# kiosk_buttons_revA.net
KiCad netlist of a schematic drawn in EAGLE
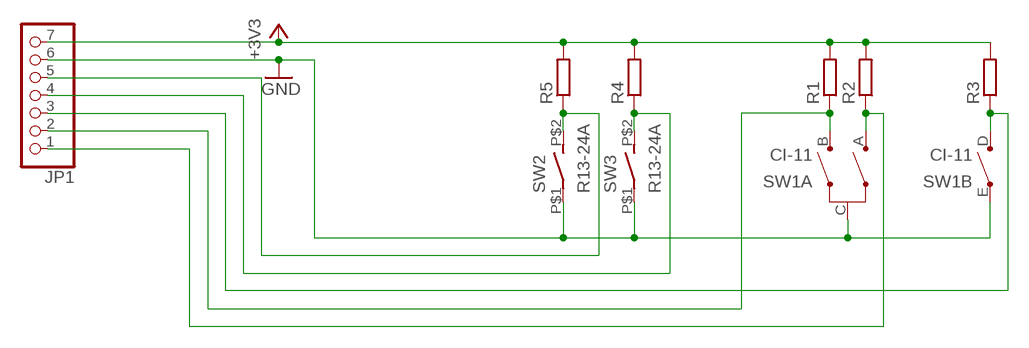
[diagram p0: schematic, sheet 1]

(export (version "E")
  (design (tool "Eeschema 10.0.6"))
  (components
    (comp (ref "JP1")
      (value "PINHD-1X7")
      (footprint "eagle-import:1X07")
      (libsource (lib "eagle-import") (part "PINHD-1X7"))
    )
    (comp (ref "R1")
      (value "R-EU_0204/2V")
      (footprint "eagle-import:0204V")
      (libsource (lib "eagle-import") (part "R-EU_0204/2V"))
    )
    (comp (ref "R2")
      (value "R-EU_0204/2V")
      (footprint "eagle-import:0204V")
      (libsource (lib "eagle-import") (part "R-EU_0204/2V"))
    )
    (comp (ref "R3")
      (value "R-EU_0204/2V")
      (footprint "eagle-import:0204V")
      (libsource (lib "eagle-import") (part "R-EU_0204/2V"))
    )
    (comp (ref "R4")
      (value "R-EU_0204/2V")
      (footprint "eagle-import:0204V")
      (libsource (lib "eagle-import") (part "R-EU_0204/2V"))
    )
    (comp (ref "R5")
      (value "R-EU_0204/2V")
      (footprint "eagle-import:0204V")
      (libsource (lib "eagle-import") (part "R-EU_0204/2V"))
    )
    (comp (ref "SW1")
      (value "CI-11")
      (footprint "eagle-import:CI-11")
      (libsource (lib "eagle-import") (part "CI-11"))
    )
    (comp (ref "SW2")
      (value "R13-24A")
      (footprint "eagle-import:R13-24")
      (fields (field (name "MF") "SCI"))
      (libsource (lib "eagle-import") (part "R13-24A"))
    )
    (comp (ref "SW3")
      (value "R13-24A")
      (footprint "eagle-import:R13-24")
      (fields (field (name "MF") "SCI"))
      (libsource (lib "eagle-import") (part "R13-24A"))
    )
  )
  (nets
    (net (code "1") (name "+3V3") (class "Default")
      (node (ref "JP1") (pin "7") (pinfunction "7_7") (pintype "passive"))
      (node (ref "R1") (pin "2") (pinfunction "2_2") (pintype "passive"))
      (node (ref "R2") (pin "2") (pinfunction "2_2") (pintype "passive"))
      (node (ref "R3") (pin "2") (pinfunction "2_2") (pintype "passive"))
      (node (ref "R4") (pin "2") (pinfunction "2_2") (pintype "passive"))
      (node (ref "R5") (pin "2") (pinfunction "2_2") (pintype "passive"))
    )
    (net (code "2") (name "GND") (class "Default")
      (node (ref "JP1") (pin "6") (pinfunction "6_6") (pintype "passive"))
      (node (ref "SW1") (pin "C") (pinfunction "C_C") (pintype "passive"))
      (node (ref "SW1") (pin "E") (pinfunction "E_E") (pintype "passive"))
      (node (ref "SW2") (pin "P$1") (pinfunction "P_P$1") (pintype "passive"))
      (node (ref "SW3") (pin "P$1") (pinfunction "P_P$1") (pintype "passive"))
    )
    (net (code "3") (name "Net-(JP1-Pad1)") (class "Default")
      (node (ref "JP1") (pin "1") (pinfunction "1_1") (pintype "passive"))
      (node (ref "R2") (pin "1") (pinfunction "1_1") (pintype "passive"))
      (node (ref "SW1") (pin "A") (pinfunction "A_A") (pintype "passive"))
    )
    (net (code "4") (name "Net-(JP1-Pad2)") (class "Default")
      (node (ref "JP1") (pin "2") (pinfunction "2_2") (pintype "passive"))
      (node (ref "R1") (pin "1") (pinfunction "1_1") (pintype "passive"))
      (node (ref "SW1") (pin "B") (pinfunction "B_B") (pintype "passive"))
    )
    (net (code "5") (name "Net-(JP1-Pad3)") (class "Default")
      (node (ref "JP1") (pin "3") (pinfunction "3_3") (pintype "passive"))
      (node (ref "R3") (pin "1") (pinfunction "1_1") (pintype "passive"))
      (node (ref "SW1") (pin "D") (pinfunction "D_D") (pintype "passive"))
    )
    (net (code "6") (name "Net-(SW2-S)") (class "Default")
      (node (ref "JP1") (pin "5") (pinfunction "5_5") (pintype "passive"))
      (node (ref "R5") (pin "1") (pinfunction "1_1") (pintype "passive"))
      (node (ref "SW2") (pin "P$2") (pinfunction "S_P$2") (pintype "passive"))
    )
    (net (code "7") (name "Net-(SW3-S)") (class "Default")
      (node (ref "JP1") (pin "4") (pinfunction "4_4") (pintype "passive"))
      (node (ref "R4") (pin "1") (pinfunction "1_1") (pintype "passive"))
      (node (ref "SW3") (pin "P$2") (pinfunction "S_P$2") (pintype "passive"))
    )
  )
)
